# DS130-1_0-B_G-M.net
KiCad netlist of a schematic drawn in Altium Designer
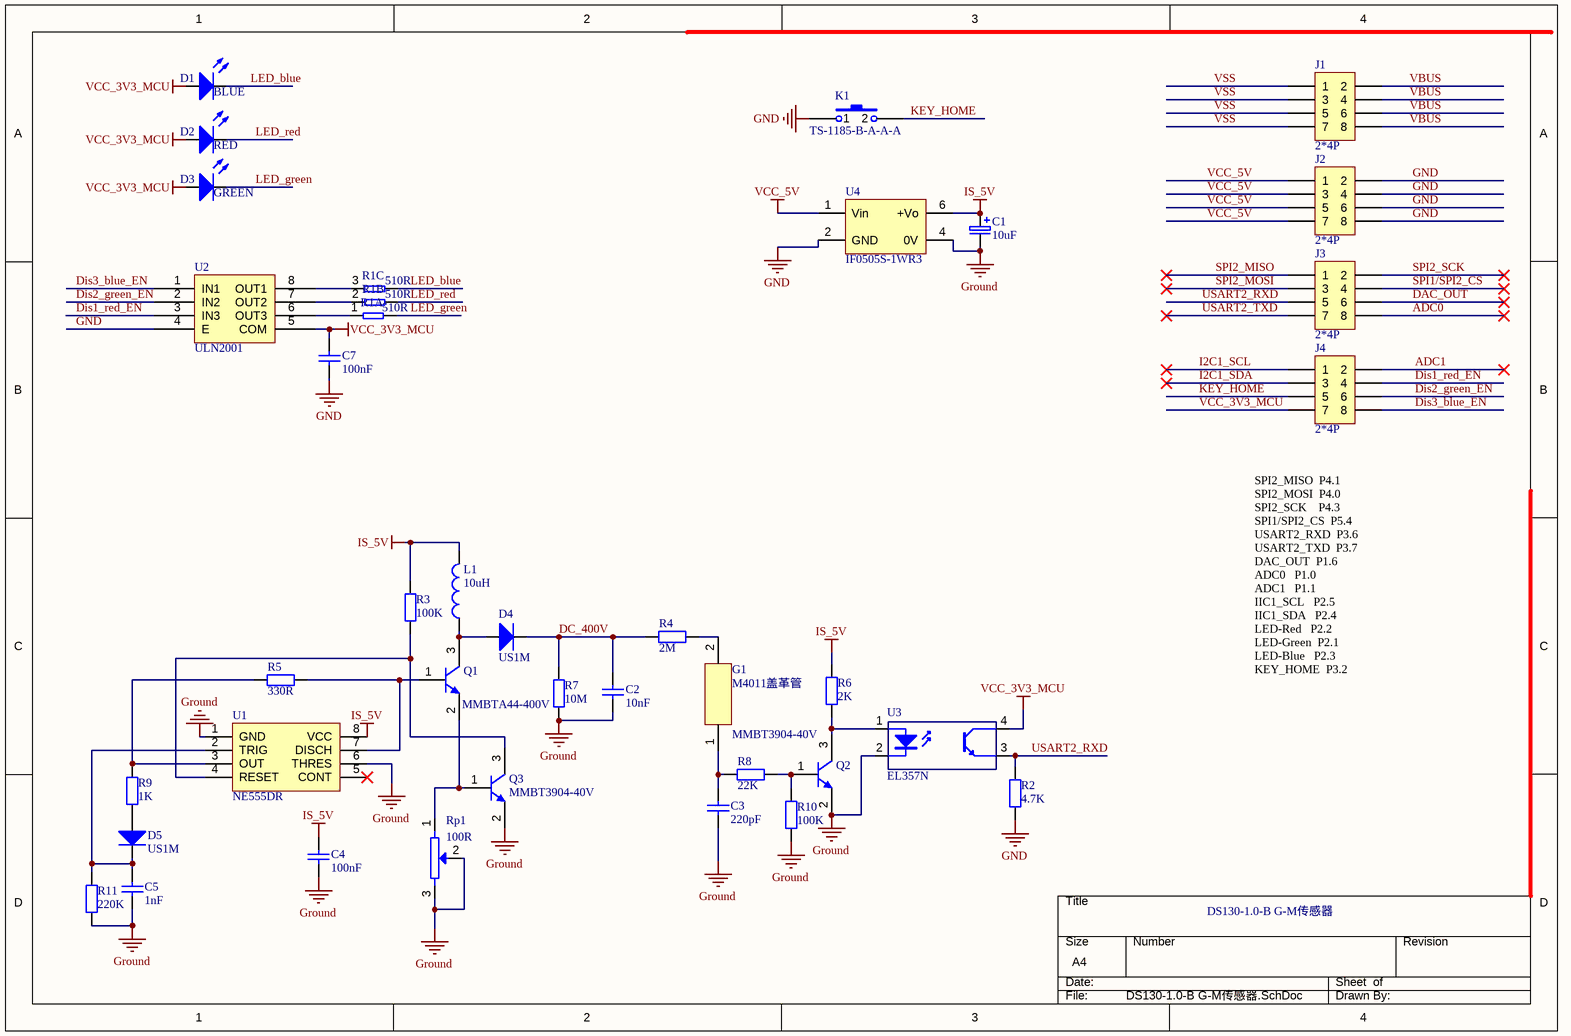
[diagram p0: DS130-1.0-B G-M传感器.SchDoc]

(export (version "E")
  (design (tool "Eeschema 10.0.6"))
  (components
    (comp (ref "C1")
      (value "10uF")
      (footprint "AVX_3216-18(1206)_SMD")
      (description "钽电容")
      (fields (field (name "Comment") "AVX_10uF/16V ±10％(C106)"))
      (libsource (lib "AD_SCH") (part "AVX_10uF/16V ±10％(C106)"))
    )
    (comp (ref "C2")
      (value "10nF")
      (footprint "1206CAP")
      (description "贴片电容")
      (fields (field (name "Comment") "MLCC 10nF 1000V ±10％ 1206"))
      (libsource (lib "AD_SCH") (part "MLCC 10nF 1000V ±10％ 1206"))
    )
    (comp (ref "C3")
      (value "220pF")
      (footprint "0805CAP")
      (description "贴片电容")
      (fields (field (name "Comment") "MLCC 220pF 500V ±10％ 0805"))
      (libsource (lib "AD_SCH") (part "MLCC 220pF 500V ±10％ 0805"))
    )
    (comp (ref "C4")
      (value "100nF")
      (footprint "0603CAP")
      (description "贴片电容")
      (fields (field (name "Comment") "SMDCAP00013"))
      (libsource (lib "AD_SCH") (part "MLCC 100nF 50V ±10％ 0603"))
    )
    (comp (ref "C5")
      (value "1nF")
      (footprint "0603CAP")
      (description "贴片电容")
      (fields (field (name "Comment") "SMDCAP00008"))
      (libsource (lib "AD_SCH") (part "MLCC 1nF 50V ±10％ 0603"))
    )
    (comp (ref "C7")
      (value "100nF")
      (footprint "0603CAP")
      (description "贴片电容")
      (fields (field (name "Comment") "SMDCAP00013"))
      (libsource (lib "AD_SCH") (part "MLCC 100nF 50V ±10％ 0603"))
    )
    (comp (ref "D1")
      (value "BLUE")
      (footprint "LED_0805")
      (description "贴片LED")
      (fields (field (name "Comment") "SMDLED00010"))
      (libsource (lib "AD_SCH") (part "Chip 蓝色LED 0805"))
    )
    (comp (ref "D2")
      (value "RED")
      (footprint "LED_0805")
      (description "贴片LED")
      (fields (field (name "Comment") "SMDLED00003"))
      (libsource (lib "AD_SCH") (part "Chip 红色LED 0805"))
    )
    (comp (ref "D3")
      (value "GREEN")
      (footprint "LED_0805")
      (description "贴片LED")
      (fields (field (name "Comment") "Chip 翠绿LED 0805"))
      (libsource (lib "AD_SCH") (part "Chip 翠绿LED 0805"))
    )
    (comp (ref "D4")
      (value "US1M")
      (footprint "SMA/DO-214AC")
      (description "快恢复/高效率二极管")
      (fields (field (name "Comment") "US1M-DO-214AC"))
      (libsource (lib "AD_SCH") (part "US1M-DO-214AC"))
    )
    (comp (ref "D5")
      (value "US1M")
      (footprint "SMA/DO-214AC")
      (description "快恢复/高效率二极管")
      (fields (field (name "Comment") "US1M-DO-214AC"))
      (libsource (lib "AD_SCH") (part "US1M-DO-214AC"))
    )
    (comp (ref "G1") (value "M4011盖革管") (footprint "M4011-90") (libsource (lib "AD_SCH") (part "M4011盖革管")))
    (comp (ref "J1")
      (value "2*4P")
      (footprint "X1321WVS-2x04J-C40D53")
      (description "双排针2x4P 立贴 1.27mm")
      (fields (field (name "Comment") "X1321WVS-2x04J-C40D53"))
      (libsource (lib "AD_SCH") (part "X1321WVS-2x04J-C40D53"))
    )
    (comp (ref "J2")
      (value "2*4P")
      (footprint "X1321WVS-2x04J-C40D53")
      (description "双排针2x4P 立贴 1.27mm")
      (fields (field (name "Comment") "X1321WVS-2x04J-C40D53"))
      (libsource (lib "AD_SCH") (part "X1321WVS-2x04J-C40D53"))
    )
    (comp (ref "J3")
      (value "2*4P")
      (footprint "X1321WVS-2x04J-C40D53")
      (description "双排针2x4P 立贴 1.27mm")
      (fields (field (name "Comment") "X1321WVS-2x04J-C40D53"))
      (libsource (lib "AD_SCH") (part "X1321WVS-2x04J-C40D53"))
    )
    (comp (ref "J4")
      (value "2*4P")
      (footprint "X1321WVS-2x04J-C40D53")
      (description "双排针2x4P 立贴 1.27mm")
      (fields (field (name "Comment") "X1321WVS-2x04J-C40D53"))
      (libsource (lib "AD_SCH") (part "X1321WVS-2x04J-C40D53"))
    )
    (comp (ref "K1")
      (value "TS-1185-B-A-A-A")
      (footprint "KEY_TS-1185-x-A-A-A")
      (description "轻触开关")
      (libsource (lib "AD_SCH") (part "TS-1185-B-A-A-A"))
    )
    (comp (ref "L1")
      (value "10uH")
      (footprint "CD32")
      (description "贴片电感")
      (fields (field (name "Comment") "CD32 10uH 3.5*3*2mm SMD"))
      (libsource (lib "AD_SCH") (part "CD32 10uH 3.5*3*2mm SMD"))
    )
    (comp (ref "Q1")
      (value "MMBTA44-400V")
      (footprint "SOT23")
      (description "BJT")
      (fields (field (name "Comment") "MMBTA44"))
      (libsource (lib "AD_SCH") (part "MMBTA44"))
    )
    (comp (ref "Q2")
      (value "MMBT3904-40V")
      (footprint "SOT23")
      (description "BJT")
      (fields (field (name "Comment") "MMBT3904"))
      (libsource (lib "AD_SCH") (part "MMBT3904"))
    )
    (comp (ref "Q3")
      (value "MMBT3904-40V")
      (footprint "SOT23")
      (description "BJT")
      (fields (field (name "Comment") "MMBT3904"))
      (libsource (lib "AD_SCH") (part "MMBT3904"))
    )
    (comp (ref "R1")
      (value "510R")
      (footprint "0603RES_Pack4")
      (description "贴片排阻")
      (fields (field (name "Comment") "SMDRES05003"))
      (libsource (lib "AD_SCH") (part "Chip R*4 510R 1/16W ±5％ 0603"))
    )
    (comp (ref "R2")
      (value "4.7K")
      (footprint "0603RES")
      (description "贴片电阻")
      (fields (field (name "Comment") "Chip 4.7K 1/16W ±1％ 0603"))
      (libsource (lib "AD_SCH") (part "Chip 4.7K 1/16W ±1％ 0603"))
    )
    (comp (ref "R3")
      (value "100K")
      (footprint "0603RES")
      (description "贴片电阻")
      (fields (field (name "Comment") "SMDRES00071"))
      (libsource (lib "AD_SCH") (part "Chip 100K 1/16W ±1％ 0603"))
    )
    (comp (ref "R4")
      (value "2M")
      (footprint "0805RES")
      (description "贴片电阻")
      (fields (field (name "Comment") "SMDRES00088"))
      (libsource (lib "AD_SCH") (part "Chip 2M 1/10W ±1％ 0805"))
    )
    (comp (ref "R5")
      (value "330R")
      (footprint "0603RES")
      (description "贴片电阻")
      (fields (field (name "Comment") "SMDRES00023"))
      (libsource (lib "AD_SCH") (part "Chip 330R 1/16W ±1％ 0603"))
    )
    (comp (ref "R6")
      (value "2K")
      (footprint "0603RES")
      (description "贴片电阻")
      (fields (field (name "Comment") "SMDRES00042"))
      (libsource (lib "AD_SCH") (part "Chip 2K 1/16W ±1％ 0603"))
    )
    (comp (ref "R7")
      (value "10M")
      (footprint "0805RES")
      (description "贴片电阻")
      (fields (field (name "Comment") "SMDRES00092"))
      (libsource (lib "AD_SCH") (part "Chip 10M 1/10W ±5％ 0805"))
    )
    (comp (ref "R8")
      (value "22K")
      (footprint "0603RES")
      (description "贴片电阻")
      (fields (field (name "Comment") "SMDRES00108"))
      (libsource (lib "AD_SCH") (part "Chip 22K 1/16W ±1％ 0603"))
    )
    (comp (ref "R9")
      (value "1K")
      (footprint "0603RES")
      (description "贴片电阻")
      (fields (field (name "Comment") "SMDRES00034"))
      (libsource (lib "AD_SCH") (part "Chip 1K 1/16W ±1％ 0603"))
    )
    (comp (ref "R10")
      (value "100K")
      (footprint "0603RES")
      (description "贴片电阻")
      (fields (field (name "Comment") "SMDRES00071"))
      (libsource (lib "AD_SCH") (part "Chip 100K 1/16W ±1％ 0603"))
    )
    (comp (ref "R11")
      (value "220K")
      (footprint "0603RES")
      (description "贴片电阻")
      (fields (field (name "Comment") "Chip 220K 1/16W ±1％ 0603"))
      (libsource (lib "AD_SCH") (part "Chip 220K 1/16W ±1％ 0603"))
    )
    (comp (ref "Rp1")
      (value "100R")
      (footprint "RP1_B")
      (description "可调精密多圈电位器")
      (fields (field (name "Comment") "侧调 3296X  100R"))
      (libsource (lib "AD_SCH") (part "侧调 3296X  100R"))
    )
    (comp (ref "U1")
      (value "NE555DR")
      (footprint "SOP-8-120")
      (description "时基芯片")
      (libsource (lib "AD_SCH") (part "NE555DR"))
    )
    (comp (ref "U2")
      (value "ULN2001")
      (footprint "SO-8")
      (description "电机驱动芯片")
      (fields (field (name "Comment") "SMDIC000018"))
      (libsource (lib "AD_SCH") (part "ULN2001 SOP-8"))
    )
    (comp (ref "U3")
      (value "EL357N")
      (footprint "SO-4")
      (description "光耦")
      (libsource (lib "AD_SCH") (part "EL357N"))
    )
    (comp (ref "U4")
      (value "IF0505S-1WR3")
      (footprint "IF0505S-1WR3")
      (libsource (lib "AD_SCH") (part "IF0505S-1WR3"))
    )
  )
  (nets
    (net (code "1") (name "/ADC0") (class "Default")
      (node (ref "J3") (pin "8") (pinfunction "8_8") (pintype "passive+no_connect"))
    )
    (net (code "2") (name "/ADC1") (class "Default")
      (node (ref "J4") (pin "2") (pinfunction "2_2") (pintype "passive+no_connect"))
    )
    (net (code "3") (name "/DAC_OUT") (class "Default")
      (node (ref "J3") (pin "6") (pinfunction "6_6") (pintype "passive+no_connect"))
    )
    (net (code "4") (name "/DC_400V") (class "Default")
      (node (ref "C2") (pin "2") (pinfunction "2_2") (pintype "passive"))
      (node (ref "D4") (pin "2") (pinfunction "K_2") (pintype "passive"))
      (node (ref "R4") (pin "1") (pinfunction "1_1") (pintype "passive"))
      (node (ref "R7") (pin "2") (pinfunction "2_2") (pintype "passive"))
    )
    (net (code "5") (name "/Dis1_red_EN") (class "Default")
      (node (ref "J4") (pin "4") (pinfunction "4_4") (pintype "passive"))
      (node (ref "U2") (pin "3") (pinfunction "IN3_3") (pintype "passive"))
    )
    (net (code "6") (name "/Dis2_green_EN") (class "Default")
      (node (ref "J4") (pin "6") (pinfunction "6_6") (pintype "passive"))
      (node (ref "U2") (pin "2") (pinfunction "IN2_2") (pintype "passive"))
    )
    (net (code "7") (name "/Dis3_blue_EN") (class "Default")
      (node (ref "J4") (pin "8") (pinfunction "8_8") (pintype "passive"))
      (node (ref "U2") (pin "1") (pinfunction "IN1_1") (pintype "passive"))
    )
    (net (code "8") (name "/I2C1_SCL") (class "Default")
      (node (ref "J4") (pin "1") (pinfunction "1_1") (pintype "passive+no_connect"))
    )
    (net (code "9") (name "/I2C1_SDA") (class "Default")
      (node (ref "J4") (pin "3") (pinfunction "3_3") (pintype "passive+no_connect"))
    )
    (net (code "10") (name "/KEY_HOME") (class "Default")
      (node (ref "J4") (pin "5") (pinfunction "5_5") (pintype "passive"))
      (node (ref "K1") (pin "2") (pinfunction "2_2") (pintype "passive"))
    )
    (net (code "11") (name "/LED_blue") (class "Default")
      (node (ref "D1") (pin "2") (pinfunction "K_2") (pintype "passive"))
      (node (ref "R1") (pin "6") (pinfunction "6_6") (pintype "passive"))
    )
    (net (code "12") (name "/LED_green") (class "Default")
      (node (ref "D3") (pin "2") (pinfunction "K_2") (pintype "passive"))
      (node (ref "R1") (pin "8") (pinfunction "8_8") (pintype "passive"))
    )
    (net (code "13") (name "/LED_red") (class "Default")
      (node (ref "D2") (pin "2") (pinfunction "K_2") (pintype "passive"))
      (node (ref "R1") (pin "7") (pinfunction "7_7") (pintype "passive"))
    )
    (net (code "14") (name "/SPI1{slash}SPI2_CS") (class "Default")
      (node (ref "J3") (pin "4") (pinfunction "4_4") (pintype "passive+no_connect"))
    )
    (net (code "15") (name "/SPI2_MISO") (class "Default")
      (node (ref "J3") (pin "1") (pinfunction "1_1") (pintype "passive+no_connect"))
    )
    (net (code "16") (name "/SPI2_MOSI") (class "Default")
      (node (ref "J3") (pin "3") (pinfunction "3_3") (pintype "passive+no_connect"))
    )
    (net (code "17") (name "/SPI2_SCK") (class "Default")
      (node (ref "J3") (pin "2") (pinfunction "2_2") (pintype "passive+no_connect"))
    )
    (net (code "18") (name "/USART2_RXD") (class "Default")
      (node (ref "J3") (pin "5") (pinfunction "5_5") (pintype "passive"))
      (node (ref "R2") (pin "2") (pinfunction "2_2") (pintype "passive"))
      (node (ref "U3") (pin "3") (pinfunction "E_3") (pintype "passive"))
    )
    (net (code "19") (name "/USART2_TXD") (class "Default")
      (node (ref "J3") (pin "7") (pinfunction "7_7") (pintype "passive+no_connect"))
    )
    (net (code "20") (name "/VBUS") (class "Default")
      (node (ref "J1") (pin "2") (pinfunction "2_2") (pintype "passive"))
      (node (ref "J1") (pin "4") (pinfunction "4_4") (pintype "passive"))
      (node (ref "J1") (pin "6") (pinfunction "6_6") (pintype "passive"))
      (node (ref "J1") (pin "8") (pinfunction "8_8") (pintype "passive"))
    )
    (net (code "21") (name "/VSS") (class "Default")
      (node (ref "J1") (pin "1") (pinfunction "1_1") (pintype "passive"))
      (node (ref "J1") (pin "3") (pinfunction "3_3") (pintype "passive"))
      (node (ref "J1") (pin "5") (pinfunction "5_5") (pintype "passive"))
      (node (ref "J1") (pin "7") (pinfunction "7_7") (pintype "passive"))
    )
    (net (code "22") (name "GND") (class "Default")
      (node (ref "C7") (pin "2") (pinfunction "2_2") (pintype "passive"))
      (node (ref "J2") (pin "2") (pinfunction "2_2") (pintype "passive"))
      (node (ref "J2") (pin "4") (pinfunction "4_4") (pintype "passive"))
      (node (ref "J2") (pin "6") (pinfunction "6_6") (pintype "passive"))
      (node (ref "J2") (pin "8") (pinfunction "8_8") (pintype "passive"))
      (node (ref "K1") (pin "1") (pinfunction "1_1") (pintype "passive"))
      (node (ref "R2") (pin "1") (pinfunction "1_1") (pintype "passive"))
      (node (ref "U2") (pin "4") (pinfunction "E_4") (pintype "passive"))
      (node (ref "U4") (pin "2") (pinfunction "GND_2") (pintype "passive"))
    )
    (net (code "23") (name "Ground") (class "Default")
      (node (ref "C1") (pin "2") (pinfunction "2_2") (pintype "passive"))
      (node (ref "C2") (pin "1") (pinfunction "1_1") (pintype "passive"))
      (node (ref "C3") (pin "1") (pinfunction "1_1") (pintype "passive"))
      (node (ref "C4") (pin "2") (pinfunction "2_2") (pintype "passive"))
      (node (ref "C5") (pin "1") (pinfunction "1_1") (pintype "passive"))
      (node (ref "Q2") (pin "2") (pinfunction "E_2") (pintype "passive"))
      (node (ref "Q3") (pin "2") (pinfunction "E_2") (pintype "passive"))
      (node (ref "R10") (pin "1") (pinfunction "1_1") (pintype "passive"))
      (node (ref "R11") (pin "1") (pinfunction "1_1") (pintype "passive"))
      (node (ref "R7") (pin "1") (pinfunction "1_1") (pintype "passive"))
      (node (ref "Rp1") (pin "2") (pinfunction "2_2") (pintype "passive"))
      (node (ref "Rp1") (pin "3") (pinfunction "3_3") (pintype "passive"))
      (node (ref "U1") (pin "1") (pinfunction "GND_1") (pintype "passive"))
      (node (ref "U1") (pin "6") (pinfunction "THRES_6") (pintype "passive"))
      (node (ref "U3") (pin "2") (pinfunction "K_2") (pintype "passive"))
      (node (ref "U4") (pin "4") (pinfunction "0V_4") (pintype "passive"))
    )
    (net (code "24") (name "IS_5V") (class "Default")
      (node (ref "C1") (pin "1") (pinfunction "1_1") (pintype "passive"))
      (node (ref "C4") (pin "1") (pinfunction "1_1") (pintype "passive"))
      (node (ref "L1") (pin "2") (pinfunction "2_2") (pintype "passive"))
      (node (ref "R3") (pin "2") (pinfunction "2_2") (pintype "passive"))
      (node (ref "R6") (pin "2") (pinfunction "2_2") (pintype "passive"))
      (node (ref "U1") (pin "8") (pinfunction "VCC_8") (pintype "passive"))
      (node (ref "U4") (pin "6") (pinfunction "+Vo_6") (pintype "passive"))
    )
    (net (code "25") (name "Net-(C3-Pad2)") (class "Default")
      (node (ref "C3") (pin "2") (pinfunction "2_2") (pintype "passive"))
      (node (ref "G1") (pin "1") (pinfunction "1_1") (pintype "passive"))
      (node (ref "R8") (pin "1") (pinfunction "1_1") (pintype "passive"))
    )
    (net (code "26") (name "Net-(D4-A)") (class "Default")
      (node (ref "D4") (pin "1") (pinfunction "A_1") (pintype "passive"))
      (node (ref "L1") (pin "1") (pinfunction "1_1") (pintype "passive"))
      (node (ref "Q1") (pin "3") (pinfunction "C_3") (pintype "passive"))
    )
    (net (code "27") (name "Net-(D5-A)") (class "Default")
      (node (ref "D5") (pin "1") (pinfunction "A_1") (pintype "passive"))
      (node (ref "R9") (pin "1") (pinfunction "1_1") (pintype "passive"))
    )
    (net (code "28") (name "Net-(D5-K)") (class "Default")
      (node (ref "C5") (pin "2") (pinfunction "2_2") (pintype "passive"))
      (node (ref "D5") (pin "2") (pinfunction "K_2") (pintype "passive"))
      (node (ref "R11") (pin "2") (pinfunction "2_2") (pintype "passive"))
      (node (ref "U1") (pin "2") (pinfunction "TRIG_2") (pintype "passive"))
    )
    (net (code "29") (name "Net-(G1-Pad2)") (class "Default")
      (node (ref "G1") (pin "2") (pinfunction "2_2") (pintype "passive"))
      (node (ref "R4") (pin "2") (pinfunction "2_2") (pintype "passive"))
    )
    (net (code "30") (name "Net-(Q1-B)") (class "Default")
      (node (ref "Q1") (pin "1") (pinfunction "B_1") (pintype "passive"))
      (node (ref "R5") (pin "2") (pinfunction "2_2") (pintype "passive"))
      (node (ref "U1") (pin "7") (pinfunction "DISCH_7") (pintype "passive"))
    )
    (net (code "31") (name "Net-(Q1-E)") (class "Default")
      (node (ref "Q1") (pin "2") (pinfunction "E_2") (pintype "passive"))
      (node (ref "Q3") (pin "1") (pinfunction "B_1") (pintype "passive"))
      (node (ref "Rp1") (pin "1") (pinfunction "1_1") (pintype "passive"))
    )
    (net (code "32") (name "Net-(Q2-B)") (class "Default")
      (node (ref "Q2") (pin "1") (pinfunction "B_1") (pintype "passive"))
      (node (ref "R10") (pin "2") (pinfunction "2_2") (pintype "passive"))
      (node (ref "R8") (pin "2") (pinfunction "2_2") (pintype "passive"))
    )
    (net (code "33") (name "Net-(Q2-C)") (class "Default")
      (node (ref "Q2") (pin "3") (pinfunction "C_3") (pintype "passive"))
      (node (ref "R6") (pin "1") (pinfunction "1_1") (pintype "passive"))
      (node (ref "U3") (pin "1") (pinfunction "A_1") (pintype "passive"))
    )
    (net (code "34") (name "Net-(Q3-C)") (class "Default")
      (node (ref "Q3") (pin "3") (pinfunction "C_3") (pintype "passive"))
      (node (ref "R3") (pin "1") (pinfunction "1_1") (pintype "passive"))
      (node (ref "U1") (pin "4") (pinfunction "RESET_4") (pintype "passive"))
    )
    (net (code "35") (name "Net-(U1-OUT)") (class "Default")
      (node (ref "R5") (pin "1") (pinfunction "1_1") (pintype "passive"))
      (node (ref "R9") (pin "2") (pinfunction "2_2") (pintype "passive"))
      (node (ref "U1") (pin "3") (pinfunction "OUT_3") (pintype "passive"))
    )
    (net (code "36") (name "Net-(U2-OUT1)") (class "Default")
      (node (ref "R1") (pin "3") (pinfunction "3_3") (pintype "passive"))
      (node (ref "U2") (pin "8") (pinfunction "OUT1_8") (pintype "passive"))
    )
    (net (code "37") (name "Net-(U2-OUT2)") (class "Default")
      (node (ref "R1") (pin "2") (pinfunction "2_2") (pintype "passive"))
      (node (ref "U2") (pin "7") (pinfunction "OUT2_7") (pintype "passive"))
    )
    (net (code "38") (name "Net-(U2-OUT3)") (class "Default")
      (node (ref "R1") (pin "1") (pinfunction "1_1") (pintype "passive"))
      (node (ref "U2") (pin "6") (pinfunction "OUT3_6") (pintype "passive"))
    )
    (net (code "39") (name "VCC_3V3_MCU") (class "Default")
      (node (ref "C7") (pin "1") (pinfunction "1_1") (pintype "passive"))
      (node (ref "D1") (pin "1") (pinfunction "A_1") (pintype "passive"))
      (node (ref "D2") (pin "1") (pinfunction "A_1") (pintype "passive"))
      (node (ref "D3") (pin "1") (pinfunction "A_1") (pintype "passive"))
      (node (ref "J4") (pin "7") (pinfunction "7_7") (pintype "passive"))
      (node (ref "U2") (pin "5") (pinfunction "COM_5") (pintype "passive"))
      (node (ref "U3") (pin "4") (pinfunction "C_4") (pintype "passive"))
    )
    (net (code "40") (name "VCC_5V") (class "Default")
      (node (ref "J2") (pin "1") (pinfunction "1_1") (pintype "passive"))
      (node (ref "J2") (pin "3") (pinfunction "3_3") (pintype "passive"))
      (node (ref "J2") (pin "5") (pinfunction "5_5") (pintype "passive"))
      (node (ref "J2") (pin "7") (pinfunction "7_7") (pintype "passive"))
      (node (ref "U4") (pin "1") (pinfunction "Vin_1") (pintype "passive"))
    )
    (net (code "41") (name "unconnected-(U1-CONT-Pad5)") (class "Default")
      (node (ref "U1") (pin "5") (pinfunction "CONT_5") (pintype "passive+no_connect"))
    )
  )
)
